# SunS_Power_Unit.net
KiCad netlist of a schematic drawn in Altium Designer
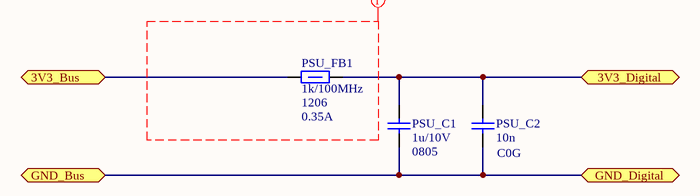
[diagram p0: SunS_Power_Unit.SchDoc]

(export (version "E")
  (design (tool "Eeschema 10.0.6"))
  (components
    (comp (ref "PSU_C1")
      (value "1u/10V")
      (footprint "SMD_Capacitor_0805")
      (description "Cap")
      (fields (field (name "PACKAGE") "0805"))
      (libsource (lib "capacitors") (part "Cap"))
    )
    (comp (ref "PSU_C2")
      (value "10n")
      (footprint "SMD_Capacitor_0402")
      (description "Cap")
      (fields (field (name "DIELECTRIC") "C0G"))
      (libsource (lib "capacitors") (part "Cap"))
    )
    (comp (ref "PSU_FB1")
      (value "1k/100MHz")
      (footprint "SMD_FerriteBead_1206")
      (description "Ferrite bead, 0402, 0.49OHM, 0.35A.")
      (fields
        (field (name "MANUFACTURERPARTNUMBER") "BLM15AX102SN1D")
        (field (name "MANUFACTURER") "Murata")
        (field (name "PACKAGE") "1206")
        (field (name "CURRENT RATING") "0.35A")
      )
      (libsource (lib "inductors") (part "BLM15AX102SN1D"))
    )
  )
  (nets
    (net (code "1") (name "/3V3_Bus") (class "Default")
      (node (ref "PSU_FB1") (pin "2") (pinfunction "2_2") (pintype "passive"))
    )
    (net (code "2") (name "/3V3_Digital") (class "Default")
      (node (ref "PSU_C1") (pin "1") (pinfunction "1_1") (pintype "passive"))
      (node (ref "PSU_C2") (pin "1") (pinfunction "1_1") (pintype "passive"))
      (node (ref "PSU_FB1") (pin "1") (pinfunction "1_1") (pintype "passive"))
    )
    (net (code "3") (name "/GND_Bus") (class "Default")
      (node (ref "PSU_C1") (pin "2") (pinfunction "2_2") (pintype "passive"))
      (node (ref "PSU_C2") (pin "2") (pinfunction "2_2") (pintype "passive"))
    )
  )
)
